# AD8318.net
KiCad netlist of a schematic drawn in Altium Designer
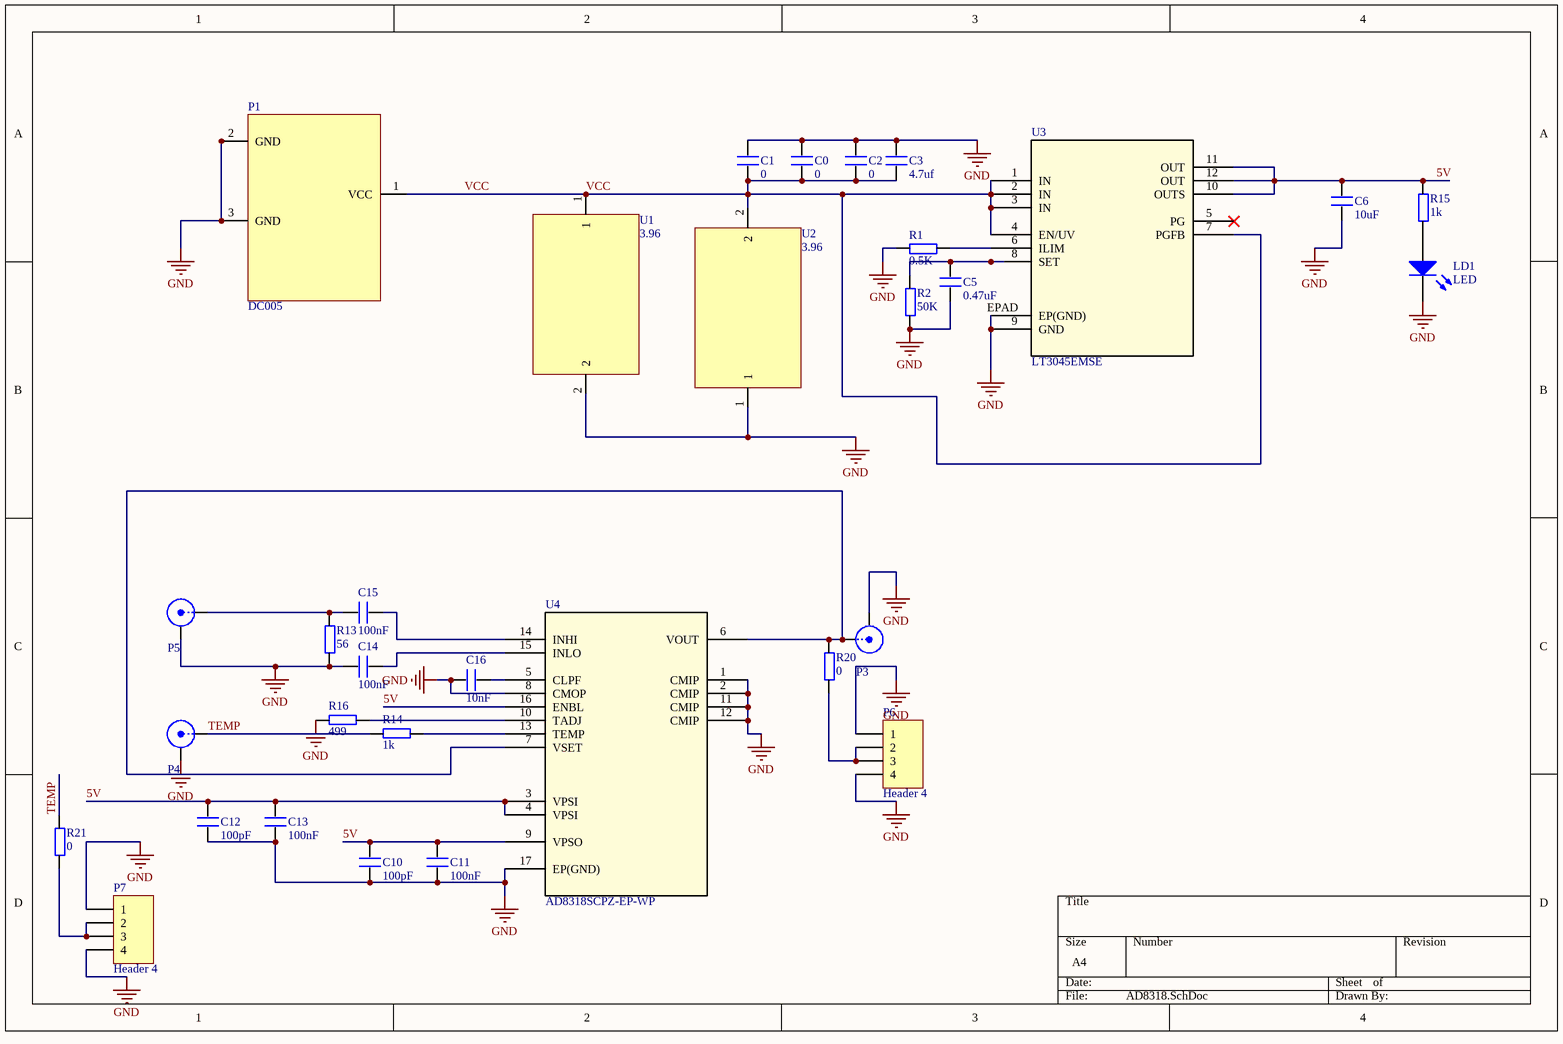
[diagram p0: AD8318.SchDoc]

(export (version "E")
  (design (tool "Eeschema 10.0.6"))
  (components
    (comp (ref "C0")
      (value "0")
      (footprint "CAP 1.5*4*8")
      (description "Capacitor")
      (libsource (lib "MYLIB") (part "C"))
    )
    (comp (ref "C1")
      (value "0")
      (footprint "CAP 1.5*4*8")
      (description "Capacitor")
      (libsource (lib "MYLIB") (part "C"))
    )
    (comp (ref "C2")
      (value "0")
      (footprint "0603C")
      (description "Capacitor")
      (libsource (lib "MYLIB") (part "C"))
    )
    (comp (ref "C3")
      (value "4.7uf")
      (footprint "0603C")
      (description "Capacitor")
      (libsource (lib "MYLIB") (part "C"))
    )
    (comp (ref "C5")
      (value "0.47uF")
      (footprint "0402")
      (description "Capacitor")
      (libsource (lib "MYLIB") (part "C"))
    )
    (comp (ref "C6")
      (value "10uF")
      (footprint "0402")
      (description "Capacitor")
      (libsource (lib "MYLIB") (part "C"))
    )
    (comp (ref "C10")
      (value "100pF")
      (footprint "0402")
      (description "Capacitor")
      (libsource (lib "MYLIB") (part "C"))
    )
    (comp (ref "C11")
      (value "100nF")
      (footprint "0402")
      (description "Capacitor")
      (libsource (lib "MYLIB") (part "C"))
    )
    (comp (ref "C12")
      (value "100pF")
      (footprint "0402")
      (description "Capacitor")
      (libsource (lib "MYLIB") (part "C"))
    )
    (comp (ref "C13")
      (value "100nF")
      (footprint "0402")
      (description "Capacitor")
      (libsource (lib "MYLIB") (part "C"))
    )
    (comp (ref "C14")
      (value "100nF")
      (footprint "0402")
      (description "Capacitor")
      (libsource (lib "MYLIB") (part "C"))
    )
    (comp (ref "C15")
      (value "100nF")
      (footprint "0402")
      (description "Capacitor")
      (libsource (lib "MYLIB") (part "C"))
    )
    (comp (ref "C16")
      (value "10nF")
      (footprint "0402")
      (description "Capacitor")
      (libsource (lib "MYLIB") (part "C"))
    )
    (comp (ref "LD1")
      (value "LED")
      (footprint "SMDLED")
      (description "Typical RED, GREEN, YELLOW, AMBER GaAs LED")
      (fields (field (name "PUBLISHER") "Altium Limited"))
      (libsource (lib "MYLIB") (part "LED"))
    )
    (comp (ref "P1") (value "DC005") (footprint "DC10B") (libsource (lib "MYLIB") (part "DC005")))
    (comp (ref "P3")
      (value "SMA")
      (footprint "SMA")
      (description "SMA Connector")
      (libsource (lib "MYLIB") (part "SMA"))
    )
    (comp (ref "P4")
      (value "SMA")
      (footprint "SMA")
      (description "SMA Connector")
      (libsource (lib "MYLIB") (part "SMA"))
    )
    (comp (ref "P5")
      (value "SMA")
      (footprint "SMA")
      (description "SMA Connector")
      (libsource (lib "MYLIB") (part "SMA"))
    )
    (comp (ref "P6")
      (value "Header 4")
      (footprint "HDR1X4")
      (description "Header, 4-Pin")
      (fields (field (name "PUBLISHER") "Altium Limited"))
      (libsource (lib "MYLIB") (part "Header 4"))
    )
    (comp (ref "P7")
      (value "Header 4")
      (footprint "HDR1X4")
      (description "Header, 4-Pin")
      (fields (field (name "PUBLISHER") "Altium Limited"))
      (libsource (lib "MYLIB") (part "Header 4"))
    )
    (comp (ref "R1")
      (value "0.5K")
      (footprint "0402")
      (description "Resistor")
      (libsource (lib "MYLIB") (part "Resistor"))
    )
    (comp (ref "R2")
      (value "50K")
      (footprint "0402")
      (description "Resistor")
      (libsource (lib "MYLIB") (part "Resistor"))
    )
    (comp (ref "R13")
      (value "56")
      (footprint "0402")
      (description "Resistor")
      (libsource (lib "MYLIB") (part "Resistor"))
    )
    (comp (ref "R14")
      (value "1k")
      (footprint "0402")
      (description "Resistor")
      (libsource (lib "MYLIB") (part "Resistor"))
    )
    (comp (ref "R15")
      (value "1k")
      (footprint "0603R")
      (description "Resistor")
      (libsource (lib "MYLIB") (part "Resistor"))
    )
    (comp (ref "R16")
      (value "499")
      (footprint "0402")
      (description "Resistor")
      (libsource (lib "MYLIB") (part "Resistor"))
    )
    (comp (ref "R20")
      (value "0")
      (footprint "0402")
      (description "Resistor")
      (libsource (lib "MYLIB") (part "Resistor"))
    )
    (comp (ref "R21")
      (value "0")
      (footprint "0402")
      (description "Resistor")
      (libsource (lib "MYLIB") (part "Resistor"))
    )
    (comp (ref "U1") (value "3.96") (footprint "3.96") (libsource (lib "MYLIB") (part "3.96")))
    (comp (ref "U2") (value "3.96") (footprint "3.96") (libsource (lib "") (part "3.96_1")))
    (comp (ref "U3")
      (value "LT3045EMSE")
      (footprint "MSOP12-MSE-RevG_ADI")
      (description "No Description Available")
      (fields (field (name "COPYRIGHT") "Copyright (C) 2018 Accelerated Designs. All rights reserved"))
      (libsource (lib "MYLIB") (part "LT3045EMSE"))
    )
    (comp (ref "U4")
      (value "AD8318SCPZ-EP-WP")
      (footprint "CP_16_23_ADI")
      (description "No Description Available")
      (fields (field (name "COPYRIGHT") "Copyright (C) 2018 Accelerated Designs. All rights reserved"))
      (libsource (lib "MYLIB") (part "AD8318SCPZ-EP-WP"))
    )
  )
  (nets
    (net (code "1") (name "/5V") (class "Default")
      (node (ref "C10") (pin "2") (pintype "passive"))
      (node (ref "C11") (pin "2") (pintype "passive"))
      (node (ref "C12") (pin "2") (pintype "passive"))
      (node (ref "C13") (pin "2") (pintype "passive"))
      (node (ref "C6") (pin "2") (pintype "passive"))
      (node (ref "R15") (pin "2") (pintype "passive"))
      (node (ref "U3") (pin "10") (pinfunction "OUTS_10") (pintype "passive"))
      (node (ref "U3") (pin "11") (pinfunction "OUT_11") (pintype "passive"))
      (node (ref "U3") (pin "12") (pinfunction "OUT_12") (pintype "passive"))
      (node (ref "U4") (pin "16") (pinfunction "ENBL_16") (pintype "passive"))
      (node (ref "U4") (pin "3") (pinfunction "VPSI_3") (pintype "power_in"))
      (node (ref "U4") (pin "4") (pinfunction "VPSI_4") (pintype "power_in"))
      (node (ref "U4") (pin "9") (pinfunction "VPSO_9") (pintype "power_in"))
    )
    (net (code "2") (name "/TEMP") (class "Default")
      (node (ref "P4") (pin "1") (pinfunction "X_1") (pintype "passive"))
      (node (ref "R14") (pin "2") (pintype "passive"))
      (node (ref "R21") (pin "2") (pintype "passive"))
    )
    (net (code "3") (name "/VCC") (class "Default")
      (node (ref "C0") (pin "1") (pintype "passive"))
      (node (ref "C1") (pin "1") (pintype "passive"))
      (node (ref "C2") (pin "1") (pintype "passive"))
      (node (ref "C3") (pin "1") (pintype "passive"))
      (node (ref "P1") (pin "1") (pinfunction "VCC_1") (pintype "passive"))
      (node (ref "U1") (pin "1") (pinfunction "1_1") (pintype "passive"))
      (node (ref "U2") (pin "2") (pinfunction "2_2") (pintype "passive"))
      (node (ref "U3") (pin "1") (pinfunction "IN_1") (pintype "passive"))
      (node (ref "U3") (pin "2") (pinfunction "IN_2") (pintype "passive"))
      (node (ref "U3") (pin "3") (pinfunction "IN_3") (pintype "passive"))
      (node (ref "U3") (pin "4") (pinfunction "EN/UV_4") (pintype "passive"))
      (node (ref "U3") (pin "7") (pinfunction "PGFB_7") (pintype "passive"))
    )
    (net (code "4") (name "GND") (class "Default")
      (node (ref "C0") (pin "2") (pintype "passive"))
      (node (ref "C1") (pin "2") (pintype "passive"))
      (node (ref "C10") (pin "1") (pintype "passive"))
      (node (ref "C11") (pin "1") (pintype "passive"))
      (node (ref "C12") (pin "1") (pintype "passive"))
      (node (ref "C13") (pin "1") (pintype "passive"))
      (node (ref "C14") (pin "2") (pintype "passive"))
      (node (ref "C16") (pin "2") (pintype "passive"))
      (node (ref "C2") (pin "2") (pintype "passive"))
      (node (ref "C3") (pin "2") (pintype "passive"))
      (node (ref "C5") (pin "2") (pintype "passive"))
      (node (ref "C6") (pin "1") (pintype "passive"))
      (node (ref "LD1") (pin "2") (pinfunction "K_2") (pintype "passive"))
      (node (ref "P1") (pin "2") (pinfunction "GND_2") (pintype "passive"))
      (node (ref "P1") (pin "3") (pinfunction "GND_3") (pintype "passive"))
      (node (ref "P3") (pin "2") (pinfunction "Y_2") (pintype "passive"))
      (node (ref "P4") (pin "2") (pinfunction "Y_2") (pintype "passive"))
      (node (ref "P5") (pin "2") (pinfunction "Y_2") (pintype "passive"))
      (node (ref "P6") (pin "1") (pinfunction "1_1") (pintype "passive"))
      (node (ref "P6") (pin "4") (pinfunction "4_4") (pintype "passive"))
      (node (ref "P7") (pin "1") (pinfunction "1_1") (pintype "passive"))
      (node (ref "P7") (pin "4") (pinfunction "4_4") (pintype "passive"))
      (node (ref "R1") (pin "1") (pintype "passive"))
      (node (ref "R13") (pin "1") (pintype "passive"))
      (node (ref "R16") (pin "2") (pintype "passive"))
      (node (ref "R2") (pin "1") (pintype "passive"))
      (node (ref "U1") (pin "2") (pinfunction "2_2") (pintype "passive"))
      (node (ref "U2") (pin "1") (pinfunction "1_1") (pintype "passive"))
      (node (ref "U3") (pin "9") (pinfunction "GND_9") (pintype "passive"))
      (node (ref "U3") (pin "EPAD") (pinfunction "EP(GND)_EPAD") (pintype "passive"))
      (node (ref "U4") (pin "1") (pinfunction "CMIP_1") (pintype "passive"))
      (node (ref "U4") (pin "11") (pinfunction "CMIP_11") (pintype "passive"))
      (node (ref "U4") (pin "12") (pinfunction "CMIP_12") (pintype "passive"))
      (node (ref "U4") (pin "17") (pinfunction "EP(GND)_17") (pintype "passive"))
      (node (ref "U4") (pin "2") (pinfunction "CMIP_2") (pintype "passive"))
      (node (ref "U4") (pin "8") (pinfunction "CMOP_8") (pintype "passive"))
    )
    (net (code "5") (name "Net-(LD1-A)") (class "Default")
      (node (ref "LD1") (pin "1") (pinfunction "A_1") (pintype "passive"))
      (node (ref "R15") (pin "1") (pintype "passive"))
    )
    (net (code "6") (name "Net-(P3-X)") (class "Default")
      (node (ref "P3") (pin "1") (pinfunction "X_1") (pintype "passive"))
      (node (ref "R20") (pin "2") (pintype "passive"))
      (node (ref "U4") (pin "6") (pinfunction "VOUT_6") (pintype "passive"))
      (node (ref "U4") (pin "7") (pinfunction "VSET_7") (pintype "passive"))
    )
    (net (code "7") (name "Net-(P5-X)") (class "Default")
      (node (ref "C15") (pin "1") (pintype "passive"))
      (node (ref "P5") (pin "1") (pinfunction "X_1") (pintype "passive"))
      (node (ref "R13") (pin "2") (pintype "passive"))
    )
    (net (code "8") (name "Net-(P6-Pad2)") (class "Default")
      (node (ref "P6") (pin "2") (pinfunction "2_2") (pintype "passive"))
      (node (ref "P6") (pin "3") (pinfunction "3_3") (pintype "passive"))
      (node (ref "R20") (pin "1") (pintype "passive"))
    )
    (net (code "9") (name "Net-(P7-Pad2)") (class "Default")
      (node (ref "P7") (pin "2") (pinfunction "2_2") (pintype "passive"))
      (node (ref "P7") (pin "3") (pinfunction "3_3") (pintype "passive"))
      (node (ref "R21") (pin "1") (pintype "passive"))
    )
    (net (code "10") (name "Net-(U3-ILIM)") (class "Default")
      (node (ref "R1") (pin "2") (pintype "passive"))
      (node (ref "U3") (pin "6") (pinfunction "ILIM_6") (pintype "passive"))
    )
    (net (code "11") (name "Net-(U3-SET)") (class "Default")
      (node (ref "C5") (pin "1") (pintype "passive"))
      (node (ref "R2") (pin "2") (pintype "passive"))
      (node (ref "U3") (pin "8") (pinfunction "SET_8") (pintype "passive"))
    )
    (net (code "12") (name "Net-(U4-CLPF)") (class "Default")
      (node (ref "C16") (pin "1") (pintype "passive"))
      (node (ref "U4") (pin "5") (pinfunction "CLPF_5") (pintype "passive"))
    )
    (net (code "13") (name "Net-(U4-INHI)") (class "Default")
      (node (ref "C15") (pin "2") (pintype "passive"))
      (node (ref "U4") (pin "14") (pinfunction "INHI_14") (pintype "passive"))
    )
    (net (code "14") (name "Net-(U4-INLO)") (class "Default")
      (node (ref "C14") (pin "1") (pintype "passive"))
      (node (ref "U4") (pin "15") (pinfunction "INLO_15") (pintype "passive"))
    )
    (net (code "15") (name "Net-(U4-TADJ)") (class "Default")
      (node (ref "R16") (pin "1") (pintype "passive"))
      (node (ref "U4") (pin "10") (pinfunction "TADJ_10") (pintype "passive"))
    )
    (net (code "16") (name "Net-(U4-TEMP)") (class "Default")
      (node (ref "R14") (pin "1") (pintype "passive"))
      (node (ref "U4") (pin "13") (pinfunction "TEMP_13") (pintype "passive"))
    )
    (net (code "17") (name "unconnected-(U3-PG-Pad5)") (class "Default")
      (node (ref "U3") (pin "5") (pinfunction "PG_5") (pintype "passive+no_connect"))
    )
  )
)
